# indicators.net
KiCad netlist of a schematic drawn in Altium Designer
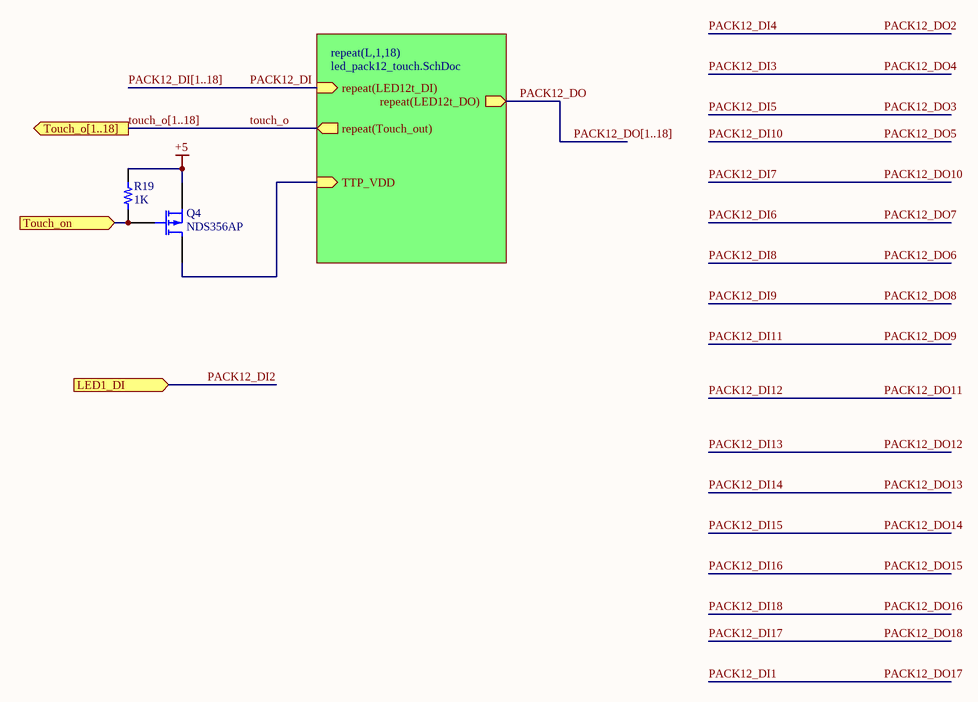
[diagram p0: indicators.SchDoc]

(export (version "E")
  (design (tool "Eeschema 10.0.6"))
  (components
    (comp (ref "Q4")
      (value "NDS356AP")
      (footprint "soT95p280x130-3n")
      (description "P-Channel MOSFET SOT23")
      (fields (field (name "PUBLISHER") "Altium Limited"))
      (libsource (lib "Miscellaneous Devices") (part "MOSFET-P"))
    )
    (comp (ref "R19")
      (value "1K")
      (footprint "0603R")
      (description "RES SMD 0603")
      (fields (field (name "PART NUMBER") "RCS0805100KFKEA"))
      (libsource (lib "lamp control-ver2") (part "Resistor"))
    )
  )
  (nets
    (net (code "20") (name "+5") (class "Default")
      (node (ref "Q4") (pin "3") (pinfunction "S_3") (pintype "passive"))
      (node (ref "R19") (pin "1") (pinfunction "1_1") (pintype "passive"))
    )
    (net (code "43") (name "/TTP_VDD") (class "Default")
      (node (ref "Q4") (pin "1") (pinfunction "D_1") (pintype "passive"))
    )
    (net (code "44") (name "/Touch_on") (class "Default")
      (node (ref "Q4") (pin "2") (pinfunction "G_2") (pintype "passive"))
      (node (ref "R19") (pin "2") (pinfunction "2_2") (pintype "passive"))
    )
  )
)
